# Sheet1.net
KiCad netlist of a schematic drawn in Altium Designer
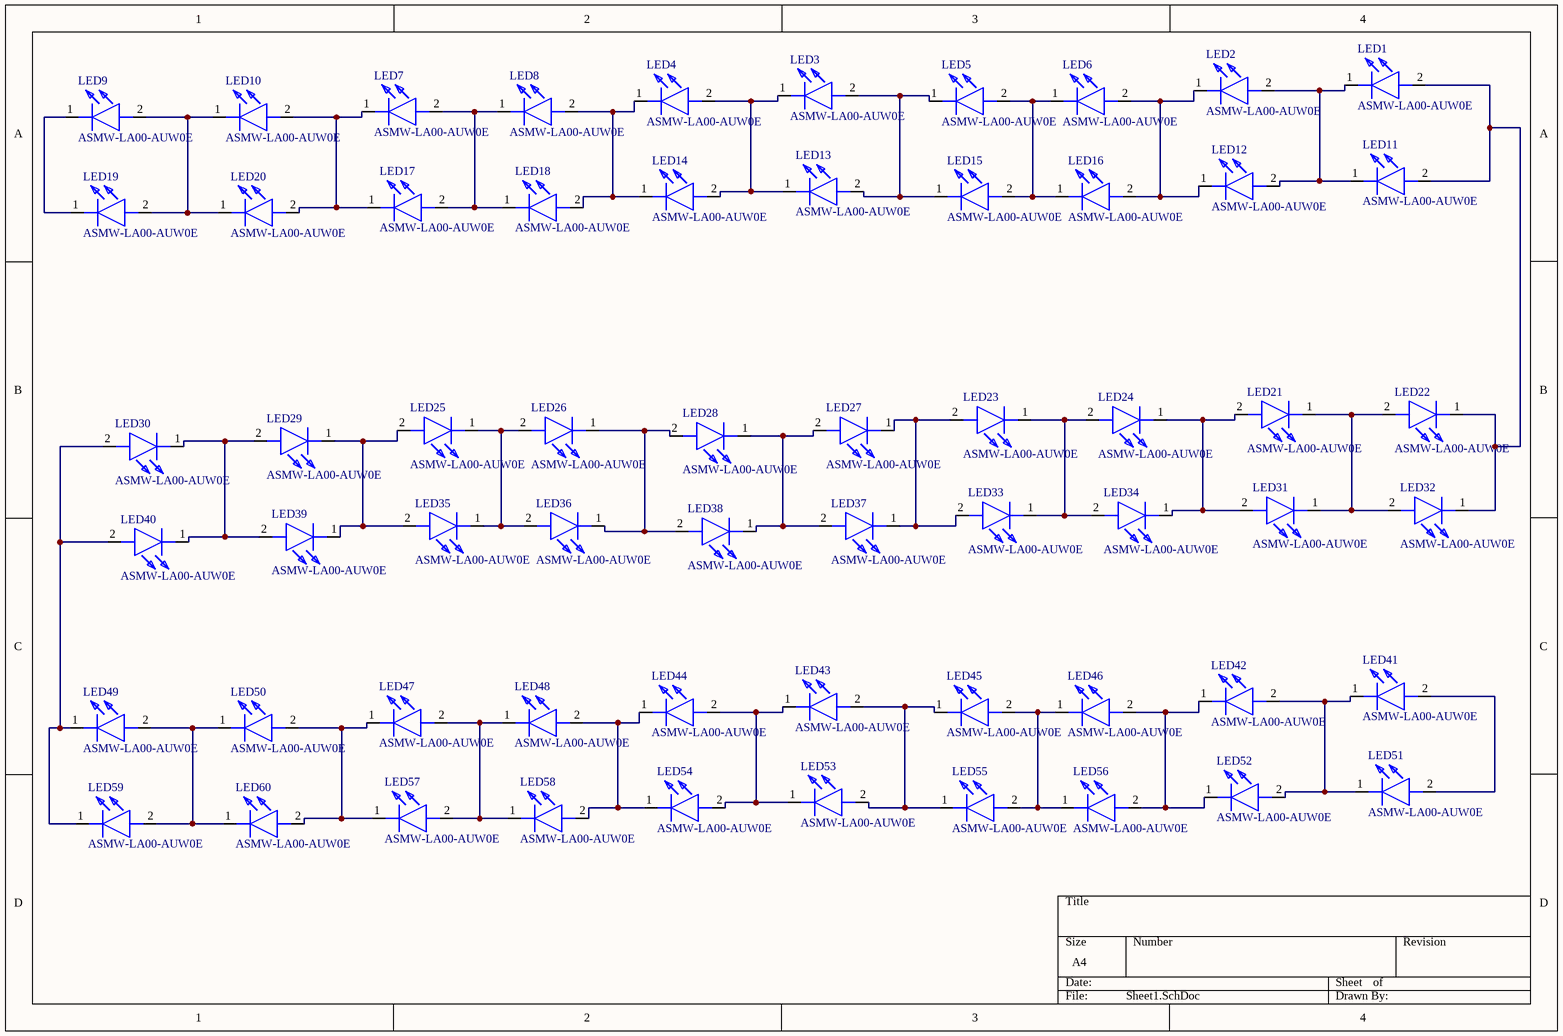
[diagram p0: Sheet1.SchDoc]

(export (version "E")
  (design (tool "Eeschema 10.0.6"))
  (components
    (comp (ref "LED1")
      (value "ASMW-LA00-AUW0E")
      (footprint "SamacSys:ASMWLA00AUW0E")
      (description "LED")
      (fields (field (name "MOUSER PART NUMBER") "630-ASMW-LA00-AUW0E"))
      (libsource (lib "*") (part "ASMW-LA00-AUW0E"))
    )
    (comp (ref "LED2")
      (value "ASMW-LA00-AUW0E")
      (footprint "SamacSys:ASMWLA00AUW0E")
      (description "LED")
      (fields (field (name "MOUSER PART NUMBER") "630-ASMW-LA00-AUW0E"))
      (libsource (lib "*") (part "ASMW-LA00-AUW0E"))
    )
    (comp (ref "LED3")
      (value "ASMW-LA00-AUW0E")
      (footprint "SamacSys:ASMWLA00AUW0E")
      (description "LED")
      (fields (field (name "MOUSER PART NUMBER") "630-ASMW-LA00-AUW0E"))
      (libsource (lib "*") (part "ASMW-LA00-AUW0E"))
    )
    (comp (ref "LED4")
      (value "ASMW-LA00-AUW0E")
      (footprint "SamacSys:ASMWLA00AUW0E")
      (description "LED")
      (fields (field (name "MOUSER PART NUMBER") "630-ASMW-LA00-AUW0E"))
      (libsource (lib "*") (part "ASMW-LA00-AUW0E"))
    )
    (comp (ref "LED5")
      (value "ASMW-LA00-AUW0E")
      (footprint "SamacSys:ASMWLA00AUW0E")
      (description "LED")
      (fields (field (name "MOUSER PART NUMBER") "630-ASMW-LA00-AUW0E"))
      (libsource (lib "*") (part "ASMW-LA00-AUW0E"))
    )
    (comp (ref "LED6")
      (value "ASMW-LA00-AUW0E")
      (footprint "SamacSys:ASMWLA00AUW0E")
      (description "LED")
      (fields (field (name "MOUSER PART NUMBER") "630-ASMW-LA00-AUW0E"))
      (libsource (lib "*") (part "ASMW-LA00-AUW0E"))
    )
    (comp (ref "LED7")
      (value "ASMW-LA00-AUW0E")
      (footprint "SamacSys:ASMWLA00AUW0E")
      (description "LED")
      (fields (field (name "MOUSER PART NUMBER") "630-ASMW-LA00-AUW0E"))
      (libsource (lib "*") (part "ASMW-LA00-AUW0E"))
    )
    (comp (ref "LED8")
      (value "ASMW-LA00-AUW0E")
      (footprint "SamacSys:ASMWLA00AUW0E")
      (description "LED")
      (fields (field (name "MOUSER PART NUMBER") "630-ASMW-LA00-AUW0E"))
      (libsource (lib "*") (part "ASMW-LA00-AUW0E"))
    )
    (comp (ref "LED9")
      (value "ASMW-LA00-AUW0E")
      (footprint "SamacSys:ASMWLA00AUW0E")
      (description "LED")
      (fields (field (name "MOUSER PART NUMBER") "630-ASMW-LA00-AUW0E"))
      (libsource (lib "*") (part "ASMW-LA00-AUW0E"))
    )
    (comp (ref "LED10")
      (value "ASMW-LA00-AUW0E")
      (footprint "SamacSys:ASMWLA00AUW0E")
      (description "LED")
      (fields (field (name "MOUSER PART NUMBER") "630-ASMW-LA00-AUW0E"))
      (libsource (lib "*") (part "ASMW-LA00-AUW0E"))
    )
    (comp (ref "LED11")
      (value "ASMW-LA00-AUW0E")
      (footprint "SamacSys:ASMWLA00AUW0E")
      (description "LED")
      (fields (field (name "MOUSER PART NUMBER") "630-ASMW-LA00-AUW0E"))
      (libsource (lib "*") (part "ASMW-LA00-AUW0E"))
    )
    (comp (ref "LED12")
      (value "ASMW-LA00-AUW0E")
      (footprint "SamacSys:ASMWLA00AUW0E")
      (description "LED")
      (fields (field (name "MOUSER PART NUMBER") "630-ASMW-LA00-AUW0E"))
      (libsource (lib "*") (part "ASMW-LA00-AUW0E"))
    )
    (comp (ref "LED13")
      (value "ASMW-LA00-AUW0E")
      (footprint "SamacSys:ASMWLA00AUW0E")
      (description "LED")
      (fields (field (name "MOUSER PART NUMBER") "630-ASMW-LA00-AUW0E"))
      (libsource (lib "*") (part "ASMW-LA00-AUW0E"))
    )
    (comp (ref "LED14")
      (value "ASMW-LA00-AUW0E")
      (footprint "SamacSys:ASMWLA00AUW0E")
      (description "LED")
      (fields (field (name "MOUSER PART NUMBER") "630-ASMW-LA00-AUW0E"))
      (libsource (lib "*") (part "ASMW-LA00-AUW0E"))
    )
    (comp (ref "LED15")
      (value "ASMW-LA00-AUW0E")
      (footprint "SamacSys:ASMWLA00AUW0E")
      (description "LED")
      (fields (field (name "MOUSER PART NUMBER") "630-ASMW-LA00-AUW0E"))
      (libsource (lib "*") (part "ASMW-LA00-AUW0E"))
    )
    (comp (ref "LED16")
      (value "ASMW-LA00-AUW0E")
      (footprint "SamacSys:ASMWLA00AUW0E")
      (description "LED")
      (fields (field (name "MOUSER PART NUMBER") "630-ASMW-LA00-AUW0E"))
      (libsource (lib "*") (part "ASMW-LA00-AUW0E"))
    )
    (comp (ref "LED17")
      (value "ASMW-LA00-AUW0E")
      (footprint "SamacSys:ASMWLA00AUW0E")
      (description "LED")
      (fields (field (name "MOUSER PART NUMBER") "630-ASMW-LA00-AUW0E"))
      (libsource (lib "*") (part "ASMW-LA00-AUW0E"))
    )
    (comp (ref "LED18")
      (value "ASMW-LA00-AUW0E")
      (footprint "SamacSys:ASMWLA00AUW0E")
      (description "LED")
      (fields (field (name "MOUSER PART NUMBER") "630-ASMW-LA00-AUW0E"))
      (libsource (lib "*") (part "ASMW-LA00-AUW0E"))
    )
    (comp (ref "LED19")
      (value "ASMW-LA00-AUW0E")
      (footprint "SamacSys:ASMWLA00AUW0E")
      (description "LED")
      (fields (field (name "MOUSER PART NUMBER") "630-ASMW-LA00-AUW0E"))
      (libsource (lib "*") (part "ASMW-LA00-AUW0E"))
    )
    (comp (ref "LED20")
      (value "ASMW-LA00-AUW0E")
      (footprint "SamacSys:ASMWLA00AUW0E")
      (description "LED")
      (fields (field (name "MOUSER PART NUMBER") "630-ASMW-LA00-AUW0E"))
      (libsource (lib "*") (part "ASMW-LA00-AUW0E"))
    )
    (comp (ref "LED21")
      (value "ASMW-LA00-AUW0E")
      (footprint "SamacSys:ASMWLA00AUW0E")
      (description "LED")
      (fields (field (name "MOUSER PART NUMBER") "630-ASMW-LA00-AUW0E"))
      (libsource (lib "*") (part "ASMW-LA00-AUW0E"))
    )
    (comp (ref "LED22")
      (value "ASMW-LA00-AUW0E")
      (footprint "SamacSys:ASMWLA00AUW0E")
      (description "LED")
      (fields (field (name "MOUSER PART NUMBER") "630-ASMW-LA00-AUW0E"))
      (libsource (lib "*") (part "ASMW-LA00-AUW0E"))
    )
    (comp (ref "LED23")
      (value "ASMW-LA00-AUW0E")
      (footprint "SamacSys:ASMWLA00AUW0E")
      (description "LED")
      (fields (field (name "MOUSER PART NUMBER") "630-ASMW-LA00-AUW0E"))
      (libsource (lib "*") (part "ASMW-LA00-AUW0E"))
    )
    (comp (ref "LED24")
      (value "ASMW-LA00-AUW0E")
      (footprint "SamacSys:ASMWLA00AUW0E")
      (description "LED")
      (fields (field (name "MOUSER PART NUMBER") "630-ASMW-LA00-AUW0E"))
      (libsource (lib "*") (part "ASMW-LA00-AUW0E"))
    )
    (comp (ref "LED25")
      (value "ASMW-LA00-AUW0E")
      (footprint "SamacSys:ASMWLA00AUW0E")
      (description "LED")
      (fields (field (name "MOUSER PART NUMBER") "630-ASMW-LA00-AUW0E"))
      (libsource (lib "*") (part "ASMW-LA00-AUW0E"))
    )
    (comp (ref "LED26")
      (value "ASMW-LA00-AUW0E")
      (footprint "SamacSys:ASMWLA00AUW0E")
      (description "LED")
      (fields (field (name "MOUSER PART NUMBER") "630-ASMW-LA00-AUW0E"))
      (libsource (lib "*") (part "ASMW-LA00-AUW0E"))
    )
    (comp (ref "LED27")
      (value "ASMW-LA00-AUW0E")
      (footprint "SamacSys:ASMWLA00AUW0E")
      (description "LED")
      (fields (field (name "MOUSER PART NUMBER") "630-ASMW-LA00-AUW0E"))
      (libsource (lib "*") (part "ASMW-LA00-AUW0E"))
    )
    (comp (ref "LED28")
      (value "ASMW-LA00-AUW0E")
      (footprint "SamacSys:ASMWLA00AUW0E")
      (description "LED")
      (fields (field (name "MOUSER PART NUMBER") "630-ASMW-LA00-AUW0E"))
      (libsource (lib "*") (part "ASMW-LA00-AUW0E"))
    )
    (comp (ref "LED29")
      (value "ASMW-LA00-AUW0E")
      (footprint "SamacSys:ASMWLA00AUW0E")
      (description "LED")
      (fields (field (name "MOUSER PART NUMBER") "630-ASMW-LA00-AUW0E"))
      (libsource (lib "*") (part "ASMW-LA00-AUW0E"))
    )
    (comp (ref "LED30")
      (value "ASMW-LA00-AUW0E")
      (footprint "SamacSys:ASMWLA00AUW0E")
      (description "LED")
      (fields (field (name "MOUSER PART NUMBER") "630-ASMW-LA00-AUW0E"))
      (libsource (lib "*") (part "ASMW-LA00-AUW0E"))
    )
    (comp (ref "LED31")
      (value "ASMW-LA00-AUW0E")
      (footprint "SamacSys:ASMWLA00AUW0E")
      (description "LED")
      (fields (field (name "MOUSER PART NUMBER") "630-ASMW-LA00-AUW0E"))
      (libsource (lib "*") (part "ASMW-LA00-AUW0E"))
    )
    (comp (ref "LED32")
      (value "ASMW-LA00-AUW0E")
      (footprint "SamacSys:ASMWLA00AUW0E")
      (description "LED")
      (fields (field (name "MOUSER PART NUMBER") "630-ASMW-LA00-AUW0E"))
      (libsource (lib "*") (part "ASMW-LA00-AUW0E"))
    )
    (comp (ref "LED33")
      (value "ASMW-LA00-AUW0E")
      (footprint "SamacSys:ASMWLA00AUW0E")
      (description "LED")
      (fields (field (name "MOUSER PART NUMBER") "630-ASMW-LA00-AUW0E"))
      (libsource (lib "*") (part "ASMW-LA00-AUW0E"))
    )
    (comp (ref "LED34")
      (value "ASMW-LA00-AUW0E")
      (footprint "SamacSys:ASMWLA00AUW0E")
      (description "LED")
      (fields (field (name "MOUSER PART NUMBER") "630-ASMW-LA00-AUW0E"))
      (libsource (lib "*") (part "ASMW-LA00-AUW0E"))
    )
    (comp (ref "LED35")
      (value "ASMW-LA00-AUW0E")
      (footprint "SamacSys:ASMWLA00AUW0E")
      (description "LED")
      (fields (field (name "MOUSER PART NUMBER") "630-ASMW-LA00-AUW0E"))
      (libsource (lib "*") (part "ASMW-LA00-AUW0E"))
    )
    (comp (ref "LED36")
      (value "ASMW-LA00-AUW0E")
      (footprint "SamacSys:ASMWLA00AUW0E")
      (description "LED")
      (fields (field (name "MOUSER PART NUMBER") "630-ASMW-LA00-AUW0E"))
      (libsource (lib "*") (part "ASMW-LA00-AUW0E"))
    )
    (comp (ref "LED37")
      (value "ASMW-LA00-AUW0E")
      (footprint "SamacSys:ASMWLA00AUW0E")
      (description "LED")
      (fields (field (name "MOUSER PART NUMBER") "630-ASMW-LA00-AUW0E"))
      (libsource (lib "*") (part "ASMW-LA00-AUW0E"))
    )
    (comp (ref "LED38")
      (value "ASMW-LA00-AUW0E")
      (footprint "SamacSys:ASMWLA00AUW0E")
      (description "LED")
      (fields (field (name "MOUSER PART NUMBER") "630-ASMW-LA00-AUW0E"))
      (libsource (lib "*") (part "ASMW-LA00-AUW0E"))
    )
    (comp (ref "LED39")
      (value "ASMW-LA00-AUW0E")
      (footprint "SamacSys:ASMWLA00AUW0E")
      (description "LED")
      (fields (field (name "MOUSER PART NUMBER") "630-ASMW-LA00-AUW0E"))
      (libsource (lib "*") (part "ASMW-LA00-AUW0E"))
    )
    (comp (ref "LED40")
      (value "ASMW-LA00-AUW0E")
      (footprint "SamacSys:ASMWLA00AUW0E")
      (description "LED")
      (fields (field (name "MOUSER PART NUMBER") "630-ASMW-LA00-AUW0E"))
      (libsource (lib "*") (part "ASMW-LA00-AUW0E"))
    )
    (comp (ref "LED41")
      (value "ASMW-LA00-AUW0E")
      (footprint "SamacSys:ASMWLA00AUW0E")
      (description "LED")
      (fields (field (name "MOUSER PART NUMBER") "630-ASMW-LA00-AUW0E"))
      (libsource (lib "*") (part "ASMW-LA00-AUW0E"))
    )
    (comp (ref "LED42")
      (value "ASMW-LA00-AUW0E")
      (footprint "SamacSys:ASMWLA00AUW0E")
      (description "LED")
      (fields (field (name "MOUSER PART NUMBER") "630-ASMW-LA00-AUW0E"))
      (libsource (lib "*") (part "ASMW-LA00-AUW0E"))
    )
    (comp (ref "LED43")
      (value "ASMW-LA00-AUW0E")
      (footprint "SamacSys:ASMWLA00AUW0E")
      (description "LED")
      (fields (field (name "MOUSER PART NUMBER") "630-ASMW-LA00-AUW0E"))
      (libsource (lib "*") (part "ASMW-LA00-AUW0E"))
    )
    (comp (ref "LED44")
      (value "ASMW-LA00-AUW0E")
      (footprint "SamacSys:ASMWLA00AUW0E")
      (description "LED")
      (fields (field (name "MOUSER PART NUMBER") "630-ASMW-LA00-AUW0E"))
      (libsource (lib "*") (part "ASMW-LA00-AUW0E"))
    )
    (comp (ref "LED45")
      (value "ASMW-LA00-AUW0E")
      (footprint "SamacSys:ASMWLA00AUW0E")
      (description "LED")
      (fields (field (name "MOUSER PART NUMBER") "630-ASMW-LA00-AUW0E"))
      (libsource (lib "*") (part "ASMW-LA00-AUW0E"))
    )
    (comp (ref "LED46")
      (value "ASMW-LA00-AUW0E")
      (footprint "SamacSys:ASMWLA00AUW0E")
      (description "LED")
      (fields (field (name "MOUSER PART NUMBER") "630-ASMW-LA00-AUW0E"))
      (libsource (lib "*") (part "ASMW-LA00-AUW0E"))
    )
    (comp (ref "LED47")
      (value "ASMW-LA00-AUW0E")
      (footprint "SamacSys:ASMWLA00AUW0E")
      (description "LED")
      (fields (field (name "MOUSER PART NUMBER") "630-ASMW-LA00-AUW0E"))
      (libsource (lib "*") (part "ASMW-LA00-AUW0E"))
    )
    (comp (ref "LED48")
      (value "ASMW-LA00-AUW0E")
      (footprint "SamacSys:ASMWLA00AUW0E")
      (description "LED")
      (fields (field (name "MOUSER PART NUMBER") "630-ASMW-LA00-AUW0E"))
      (libsource (lib "*") (part "ASMW-LA00-AUW0E"))
    )
    (comp (ref "LED49")
      (value "ASMW-LA00-AUW0E")
      (footprint "SamacSys:ASMWLA00AUW0E")
      (description "LED")
      (fields (field (name "MOUSER PART NUMBER") "630-ASMW-LA00-AUW0E"))
      (libsource (lib "*") (part "ASMW-LA00-AUW0E"))
    )
    (comp (ref "LED50")
      (value "ASMW-LA00-AUW0E")
      (footprint "SamacSys:ASMWLA00AUW0E")
      (description "LED")
      (fields (field (name "MOUSER PART NUMBER") "630-ASMW-LA00-AUW0E"))
      (libsource (lib "*") (part "ASMW-LA00-AUW0E"))
    )
    (comp (ref "LED51")
      (value "ASMW-LA00-AUW0E")
      (footprint "SamacSys:ASMWLA00AUW0E")
      (description "LED")
      (fields (field (name "MOUSER PART NUMBER") "630-ASMW-LA00-AUW0E"))
      (libsource (lib "*") (part "ASMW-LA00-AUW0E"))
    )
    (comp (ref "LED52")
      (value "ASMW-LA00-AUW0E")
      (footprint "SamacSys:ASMWLA00AUW0E")
      (description "LED")
      (fields (field (name "MOUSER PART NUMBER") "630-ASMW-LA00-AUW0E"))
      (libsource (lib "*") (part "ASMW-LA00-AUW0E"))
    )
    (comp (ref "LED53")
      (value "ASMW-LA00-AUW0E")
      (footprint "SamacSys:ASMWLA00AUW0E")
      (description "LED")
      (fields (field (name "MOUSER PART NUMBER") "630-ASMW-LA00-AUW0E"))
      (libsource (lib "*") (part "ASMW-LA00-AUW0E"))
    )
    (comp (ref "LED54")
      (value "ASMW-LA00-AUW0E")
      (footprint "SamacSys:ASMWLA00AUW0E")
      (description "LED")
      (fields (field (name "MOUSER PART NUMBER") "630-ASMW-LA00-AUW0E"))
      (libsource (lib "*") (part "ASMW-LA00-AUW0E"))
    )
    (comp (ref "LED55")
      (value "ASMW-LA00-AUW0E")
      (footprint "SamacSys:ASMWLA00AUW0E")
      (description "LED")
      (fields (field (name "MOUSER PART NUMBER") "630-ASMW-LA00-AUW0E"))
      (libsource (lib "*") (part "ASMW-LA00-AUW0E"))
    )
    (comp (ref "LED56")
      (value "ASMW-LA00-AUW0E")
      (footprint "SamacSys:ASMWLA00AUW0E")
      (description "LED")
      (fields (field (name "MOUSER PART NUMBER") "630-ASMW-LA00-AUW0E"))
      (libsource (lib "*") (part "ASMW-LA00-AUW0E"))
    )
    (comp (ref "LED57")
      (value "ASMW-LA00-AUW0E")
      (footprint "SamacSys:ASMWLA00AUW0E")
      (description "LED")
      (fields (field (name "MOUSER PART NUMBER") "630-ASMW-LA00-AUW0E"))
      (libsource (lib "*") (part "ASMW-LA00-AUW0E"))
    )
    (comp (ref "LED58")
      (value "ASMW-LA00-AUW0E")
      (footprint "SamacSys:ASMWLA00AUW0E")
      (description "LED")
      (fields (field (name "MOUSER PART NUMBER") "630-ASMW-LA00-AUW0E"))
      (libsource (lib "*") (part "ASMW-LA00-AUW0E"))
    )
    (comp (ref "LED59")
      (value "ASMW-LA00-AUW0E")
      (footprint "SamacSys:ASMWLA00AUW0E")
      (description "LED")
      (fields (field (name "MOUSER PART NUMBER") "630-ASMW-LA00-AUW0E"))
      (libsource (lib "*") (part "ASMW-LA00-AUW0E"))
    )
    (comp (ref "LED60")
      (value "ASMW-LA00-AUW0E")
      (footprint "SamacSys:ASMWLA00AUW0E")
      (description "LED")
      (fields (field (name "MOUSER PART NUMBER") "630-ASMW-LA00-AUW0E"))
      (libsource (lib "*") (part "ASMW-LA00-AUW0E"))
    )
  )
  (nets
    (net (code "1") (name "Net-(LED1-A)") (class "Default")
      (node (ref "LED1") (pin "2") (pinfunction "A_2") (pintype "passive"))
      (node (ref "LED11") (pin "2") (pinfunction "A_2") (pintype "passive"))
      (node (ref "LED22") (pin "1") (pinfunction "K_1") (pintype "passive"))
      (node (ref "LED32") (pin "1") (pinfunction "K_1") (pintype "passive"))
    )
    (net (code "2") (name "Net-(LED1-K)") (class "Default")
      (node (ref "LED1") (pin "1") (pinfunction "K_1") (pintype "passive"))
      (node (ref "LED11") (pin "1") (pinfunction "K_1") (pintype "passive"))
      (node (ref "LED12") (pin "2") (pinfunction "A_2") (pintype "passive"))
      (node (ref "LED2") (pin "2") (pinfunction "A_2") (pintype "passive"))
    )
    (net (code "3") (name "Net-(LED10-A)") (class "Default")
      (node (ref "LED10") (pin "2") (pinfunction "A_2") (pintype "passive"))
      (node (ref "LED17") (pin "1") (pinfunction "K_1") (pintype "passive"))
      (node (ref "LED20") (pin "2") (pinfunction "A_2") (pintype "passive"))
      (node (ref "LED7") (pin "1") (pinfunction "K_1") (pintype "passive"))
    )
    (net (code "4") (name "Net-(LED10-K)") (class "Default")
      (node (ref "LED10") (pin "1") (pinfunction "K_1") (pintype "passive"))
      (node (ref "LED19") (pin "2") (pinfunction "A_2") (pintype "passive"))
      (node (ref "LED20") (pin "1") (pinfunction "K_1") (pintype "passive"))
      (node (ref "LED9") (pin "2") (pinfunction "A_2") (pintype "passive"))
    )
    (net (code "5") (name "Net-(LED12-K)") (class "Default")
      (node (ref "LED12") (pin "1") (pinfunction "K_1") (pintype "passive"))
      (node (ref "LED16") (pin "2") (pinfunction "A_2") (pintype "passive"))
      (node (ref "LED2") (pin "1") (pinfunction "K_1") (pintype "passive"))
      (node (ref "LED6") (pin "2") (pinfunction "A_2") (pintype "passive"))
    )
    (net (code "6") (name "Net-(LED13-A)") (class "Default")
      (node (ref "LED13") (pin "2") (pinfunction "A_2") (pintype "passive"))
      (node (ref "LED15") (pin "1") (pinfunction "K_1") (pintype "passive"))
      (node (ref "LED3") (pin "2") (pinfunction "A_2") (pintype "passive"))
      (node (ref "LED5") (pin "1") (pinfunction "K_1") (pintype "passive"))
    )
    (net (code "7") (name "Net-(LED13-K)") (class "Default")
      (node (ref "LED13") (pin "1") (pinfunction "K_1") (pintype "passive"))
      (node (ref "LED14") (pin "2") (pinfunction "A_2") (pintype "passive"))
      (node (ref "LED3") (pin "1") (pinfunction "K_1") (pintype "passive"))
      (node (ref "LED4") (pin "2") (pinfunction "A_2") (pintype "passive"))
    )
    (net (code "8") (name "Net-(LED14-K)") (class "Default")
      (node (ref "LED14") (pin "1") (pinfunction "K_1") (pintype "passive"))
      (node (ref "LED18") (pin "2") (pinfunction "A_2") (pintype "passive"))
      (node (ref "LED4") (pin "1") (pinfunction "K_1") (pintype "passive"))
      (node (ref "LED8") (pin "2") (pinfunction "A_2") (pintype "passive"))
    )
    (net (code "9") (name "Net-(LED15-A)") (class "Default")
      (node (ref "LED15") (pin "2") (pinfunction "A_2") (pintype "passive"))
      (node (ref "LED16") (pin "1") (pinfunction "K_1") (pintype "passive"))
      (node (ref "LED5") (pin "2") (pinfunction "A_2") (pintype "passive"))
      (node (ref "LED6") (pin "1") (pinfunction "K_1") (pintype "passive"))
    )
    (net (code "10") (name "Net-(LED17-A)") (class "Default")
      (node (ref "LED17") (pin "2") (pinfunction "A_2") (pintype "passive"))
      (node (ref "LED18") (pin "1") (pinfunction "K_1") (pintype "passive"))
      (node (ref "LED7") (pin "2") (pinfunction "A_2") (pintype "passive"))
      (node (ref "LED8") (pin "1") (pinfunction "K_1") (pintype "passive"))
    )
    (net (code "11") (name "Net-(LED19-K)") (class "Default")
      (node (ref "LED19") (pin "1") (pinfunction "K_1") (pintype "passive"))
      (node (ref "LED9") (pin "1") (pinfunction "K_1") (pintype "passive"))
    )
    (net (code "12") (name "Net-(LED21-A)") (class "Default")
      (node (ref "LED21") (pin "2") (pinfunction "A_2") (pintype "passive"))
      (node (ref "LED24") (pin "1") (pinfunction "K_1") (pintype "passive"))
      (node (ref "LED31") (pin "2") (pinfunction "A_2") (pintype "passive"))
      (node (ref "LED34") (pin "1") (pinfunction "K_1") (pintype "passive"))
    )
    (net (code "13") (name "Net-(LED21-K)") (class "Default")
      (node (ref "LED21") (pin "1") (pinfunction "K_1") (pintype "passive"))
      (node (ref "LED22") (pin "2") (pinfunction "A_2") (pintype "passive"))
      (node (ref "LED31") (pin "1") (pinfunction "K_1") (pintype "passive"))
      (node (ref "LED32") (pin "2") (pinfunction "A_2") (pintype "passive"))
    )
    (net (code "14") (name "Net-(LED23-A)") (class "Default")
      (node (ref "LED23") (pin "2") (pinfunction "A_2") (pintype "passive"))
      (node (ref "LED27") (pin "1") (pinfunction "K_1") (pintype "passive"))
      (node (ref "LED33") (pin "2") (pinfunction "A_2") (pintype "passive"))
      (node (ref "LED37") (pin "1") (pinfunction "K_1") (pintype "passive"))
    )
    (net (code "15") (name "Net-(LED23-K)") (class "Default")
      (node (ref "LED23") (pin "1") (pinfunction "K_1") (pintype "passive"))
      (node (ref "LED24") (pin "2") (pinfunction "A_2") (pintype "passive"))
      (node (ref "LED33") (pin "1") (pinfunction "K_1") (pintype "passive"))
      (node (ref "LED34") (pin "2") (pinfunction "A_2") (pintype "passive"))
    )
    (net (code "16") (name "Net-(LED25-A)") (class "Default")
      (node (ref "LED25") (pin "2") (pinfunction "A_2") (pintype "passive"))
      (node (ref "LED29") (pin "1") (pinfunction "K_1") (pintype "passive"))
      (node (ref "LED35") (pin "2") (pinfunction "A_2") (pintype "passive"))
      (node (ref "LED39") (pin "1") (pinfunction "K_1") (pintype "passive"))
    )
    (net (code "17") (name "Net-(LED25-K)") (class "Default")
      (node (ref "LED25") (pin "1") (pinfunction "K_1") (pintype "passive"))
      (node (ref "LED26") (pin "2") (pinfunction "A_2") (pintype "passive"))
      (node (ref "LED35") (pin "1") (pinfunction "K_1") (pintype "passive"))
      (node (ref "LED36") (pin "2") (pinfunction "A_2") (pintype "passive"))
    )
    (net (code "18") (name "Net-(LED26-K)") (class "Default")
      (node (ref "LED26") (pin "1") (pinfunction "K_1") (pintype "passive"))
      (node (ref "LED28") (pin "2") (pinfunction "A_2") (pintype "passive"))
      (node (ref "LED36") (pin "1") (pinfunction "K_1") (pintype "passive"))
      (node (ref "LED38") (pin "2") (pinfunction "A_2") (pintype "passive"))
    )
    (net (code "19") (name "Net-(LED27-A)") (class "Default")
      (node (ref "LED27") (pin "2") (pinfunction "A_2") (pintype "passive"))
      (node (ref "LED28") (pin "1") (pinfunction "K_1") (pintype "passive"))
      (node (ref "LED37") (pin "2") (pinfunction "A_2") (pintype "passive"))
      (node (ref "LED38") (pin "1") (pinfunction "K_1") (pintype "passive"))
    )
    (net (code "20") (name "Net-(LED29-A)") (class "Default")
      (node (ref "LED29") (pin "2") (pinfunction "A_2") (pintype "passive"))
      (node (ref "LED30") (pin "1") (pinfunction "K_1") (pintype "passive"))
      (node (ref "LED39") (pin "2") (pinfunction "A_2") (pintype "passive"))
      (node (ref "LED40") (pin "1") (pinfunction "K_1") (pintype "passive"))
    )
    (net (code "21") (name "Net-(LED30-A)") (class "Default")
      (node (ref "LED30") (pin "2") (pinfunction "A_2") (pintype "passive"))
      (node (ref "LED40") (pin "2") (pinfunction "A_2") (pintype "passive"))
      (node (ref "LED49") (pin "1") (pinfunction "K_1") (pintype "passive"))
      (node (ref "LED59") (pin "1") (pinfunction "K_1") (pintype "passive"))
    )
    (net (code "22") (name "Net-(LED41-A)") (class "Default")
      (node (ref "LED41") (pin "2") (pinfunction "A_2") (pintype "passive"))
      (node (ref "LED51") (pin "2") (pinfunction "A_2") (pintype "passive"))
    )
    (net (code "23") (name "Net-(LED41-K)") (class "Default")
      (node (ref "LED41") (pin "1") (pinfunction "K_1") (pintype "passive"))
      (node (ref "LED42") (pin "2") (pinfunction "A_2") (pintype "passive"))
      (node (ref "LED51") (pin "1") (pinfunction "K_1") (pintype "passive"))
      (node (ref "LED52") (pin "2") (pinfunction "A_2") (pintype "passive"))
    )
    (net (code "24") (name "Net-(LED42-K)") (class "Default")
      (node (ref "LED42") (pin "1") (pinfunction "K_1") (pintype "passive"))
      (node (ref "LED46") (pin "2") (pinfunction "A_2") (pintype "passive"))
      (node (ref "LED52") (pin "1") (pinfunction "K_1") (pintype "passive"))
      (node (ref "LED56") (pin "2") (pinfunction "A_2") (pintype "passive"))
    )
    (net (code "25") (name "Net-(LED43-A)") (class "Default")
      (node (ref "LED43") (pin "2") (pinfunction "A_2") (pintype "passive"))
      (node (ref "LED45") (pin "1") (pinfunction "K_1") (pintype "passive"))
      (node (ref "LED53") (pin "2") (pinfunction "A_2") (pintype "passive"))
      (node (ref "LED55") (pin "1") (pinfunction "K_1") (pintype "passive"))
    )
    (net (code "26") (name "Net-(LED43-K)") (class "Default")
      (node (ref "LED43") (pin "1") (pinfunction "K_1") (pintype "passive"))
      (node (ref "LED44") (pin "2") (pinfunction "A_2") (pintype "passive"))
      (node (ref "LED53") (pin "1") (pinfunction "K_1") (pintype "passive"))
      (node (ref "LED54") (pin "2") (pinfunction "A_2") (pintype "passive"))
    )
    (net (code "27") (name "Net-(LED44-K)") (class "Default")
      (node (ref "LED44") (pin "1") (pinfunction "K_1") (pintype "passive"))
      (node (ref "LED48") (pin "2") (pinfunction "A_2") (pintype "passive"))
      (node (ref "LED54") (pin "1") (pinfunction "K_1") (pintype "passive"))
      (node (ref "LED58") (pin "2") (pinfunction "A_2") (pintype "passive"))
    )
    (net (code "28") (name "Net-(LED45-A)") (class "Default")
      (node (ref "LED45") (pin "2") (pinfunction "A_2") (pintype "passive"))
      (node (ref "LED46") (pin "1") (pinfunction "K_1") (pintype "passive"))
      (node (ref "LED55") (pin "2") (pinfunction "A_2") (pintype "passive"))
      (node (ref "LED56") (pin "1") (pinfunction "K_1") (pintype "passive"))
    )
    (net (code "29") (name "Net-(LED47-A)") (class "Default")
      (node (ref "LED47") (pin "2") (pinfunction "A_2") (pintype "passive"))
      (node (ref "LED48") (pin "1") (pinfunction "K_1") (pintype "passive"))
      (node (ref "LED57") (pin "2") (pinfunction "A_2") (pintype "passive"))
      (node (ref "LED58") (pin "1") (pinfunction "K_1") (pintype "passive"))
    )
    (net (code "30") (name "Net-(LED47-K)") (class "Default")
      (node (ref "LED47") (pin "1") (pinfunction "K_1") (pintype "passive"))
      (node (ref "LED50") (pin "2") (pinfunction "A_2") (pintype "passive"))
      (node (ref "LED57") (pin "1") (pinfunction "K_1") (pintype "passive"))
      (node (ref "LED60") (pin "2") (pinfunction "A_2") (pintype "passive"))
    )
    (net (code "31") (name "Net-(LED49-A)") (class "Default")
      (node (ref "LED49") (pin "2") (pinfunction "A_2") (pintype "passive"))
      (node (ref "LED50") (pin "1") (pinfunction "K_1") (pintype "passive"))
      (node (ref "LED59") (pin "2") (pinfunction "A_2") (pintype "passive"))
      (node (ref "LED60") (pin "1") (pinfunction "K_1") (pintype "passive"))
    )
  )
)
